# BSB-to-Wifi.net
KiCad netlist of a schematic drawn in EAGLE
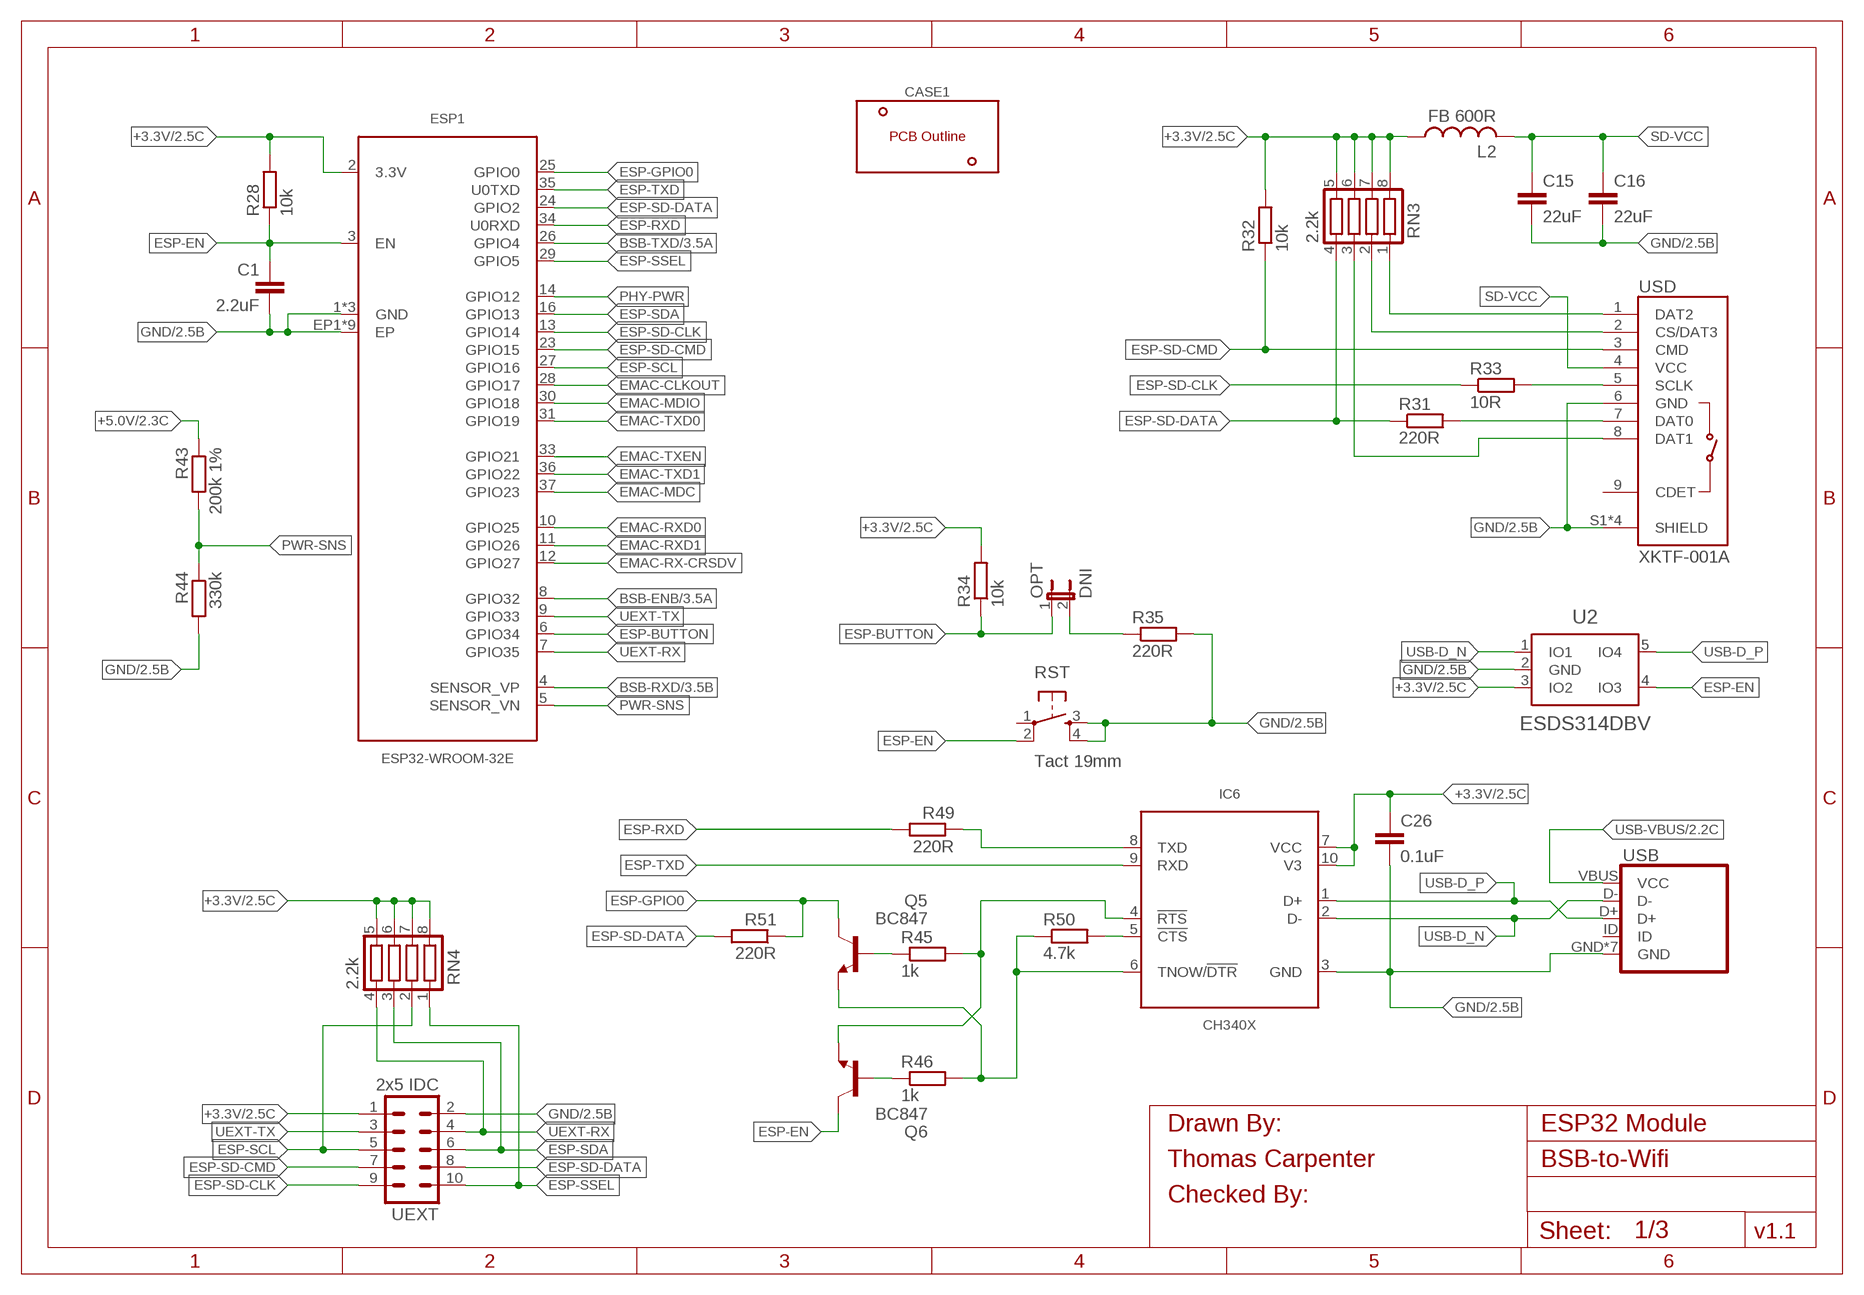
[diagram p0: schematic, sheet 1]
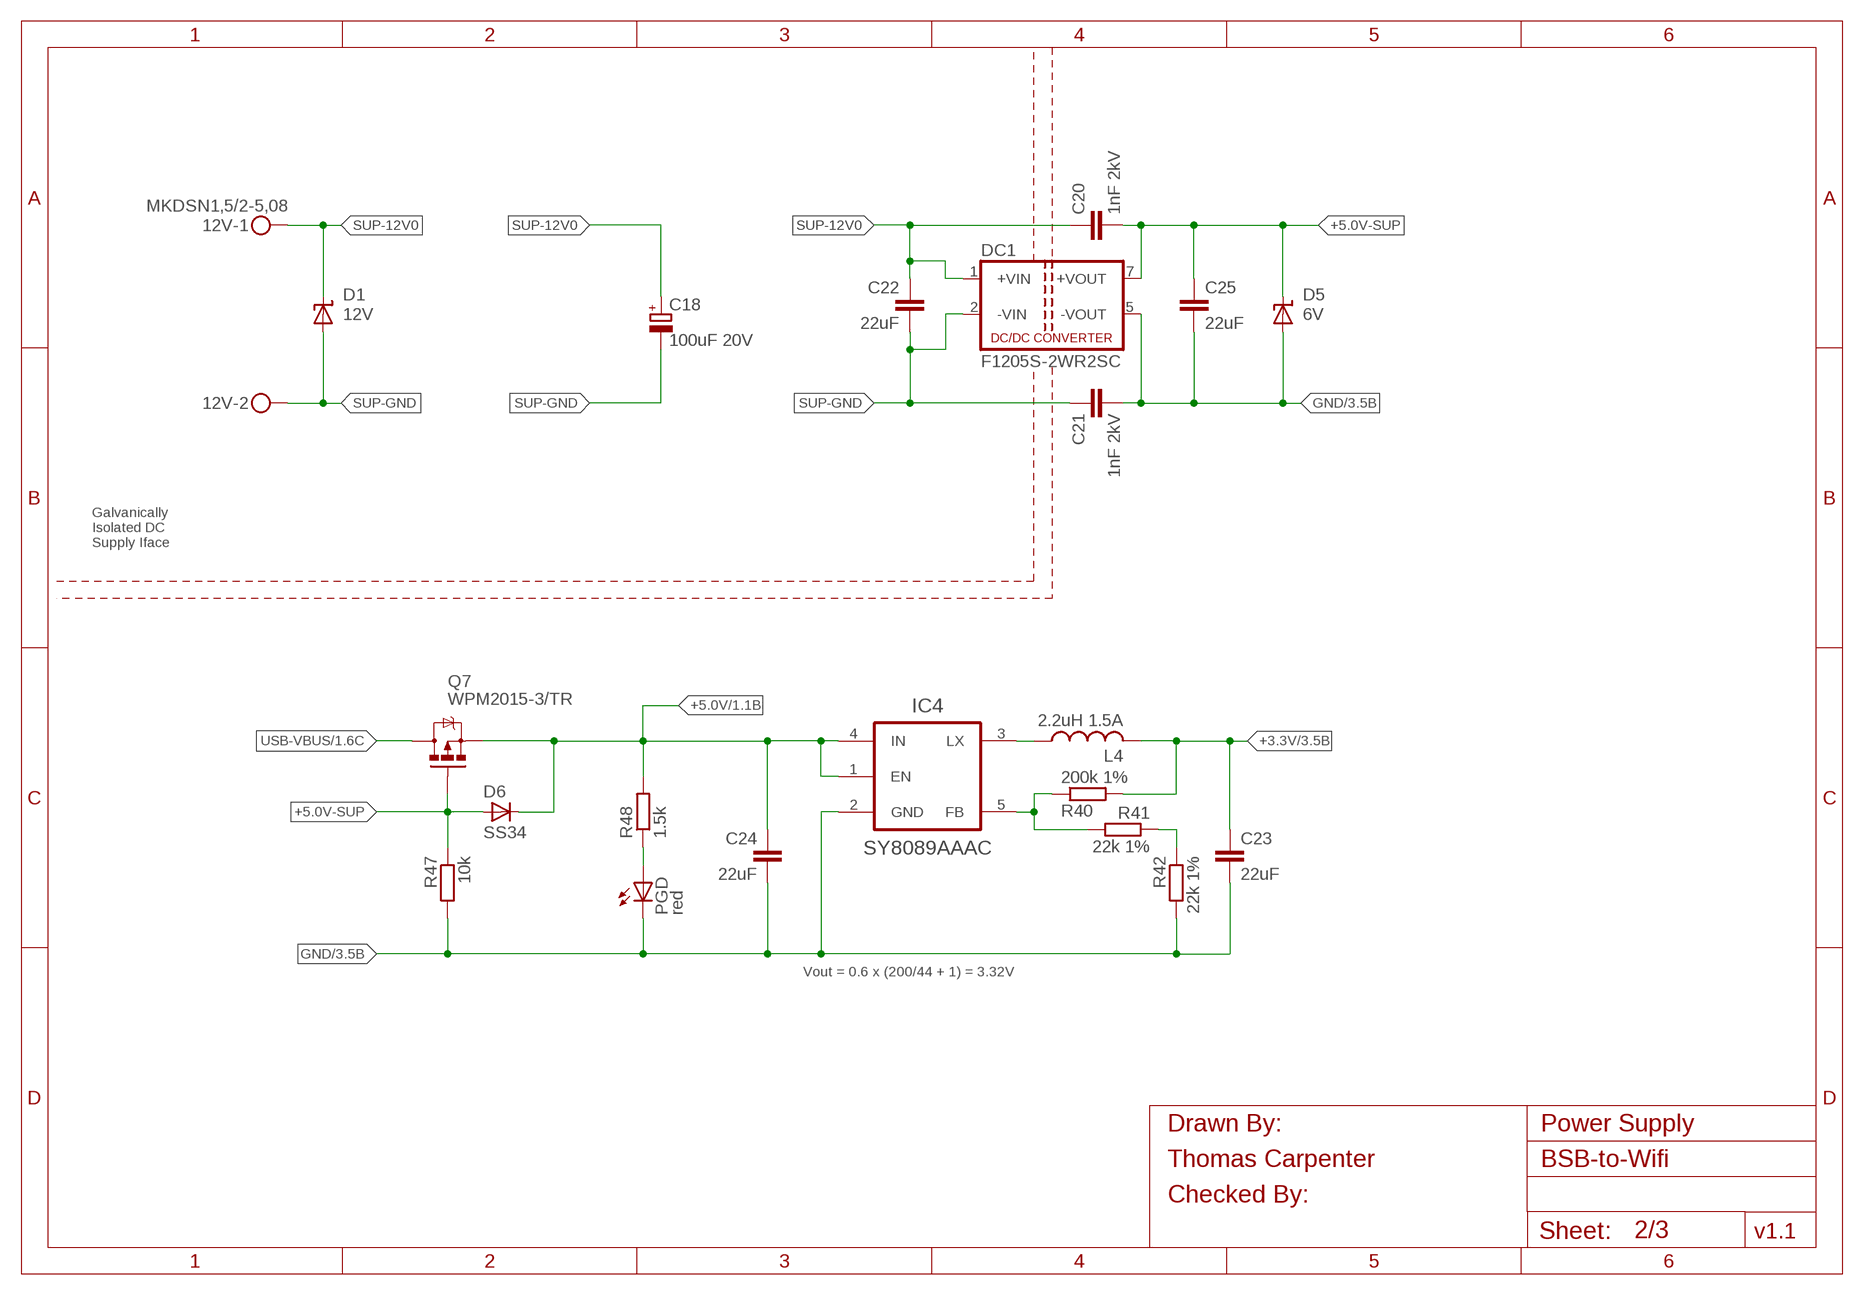
[diagram p1: schematic, sheet 2]
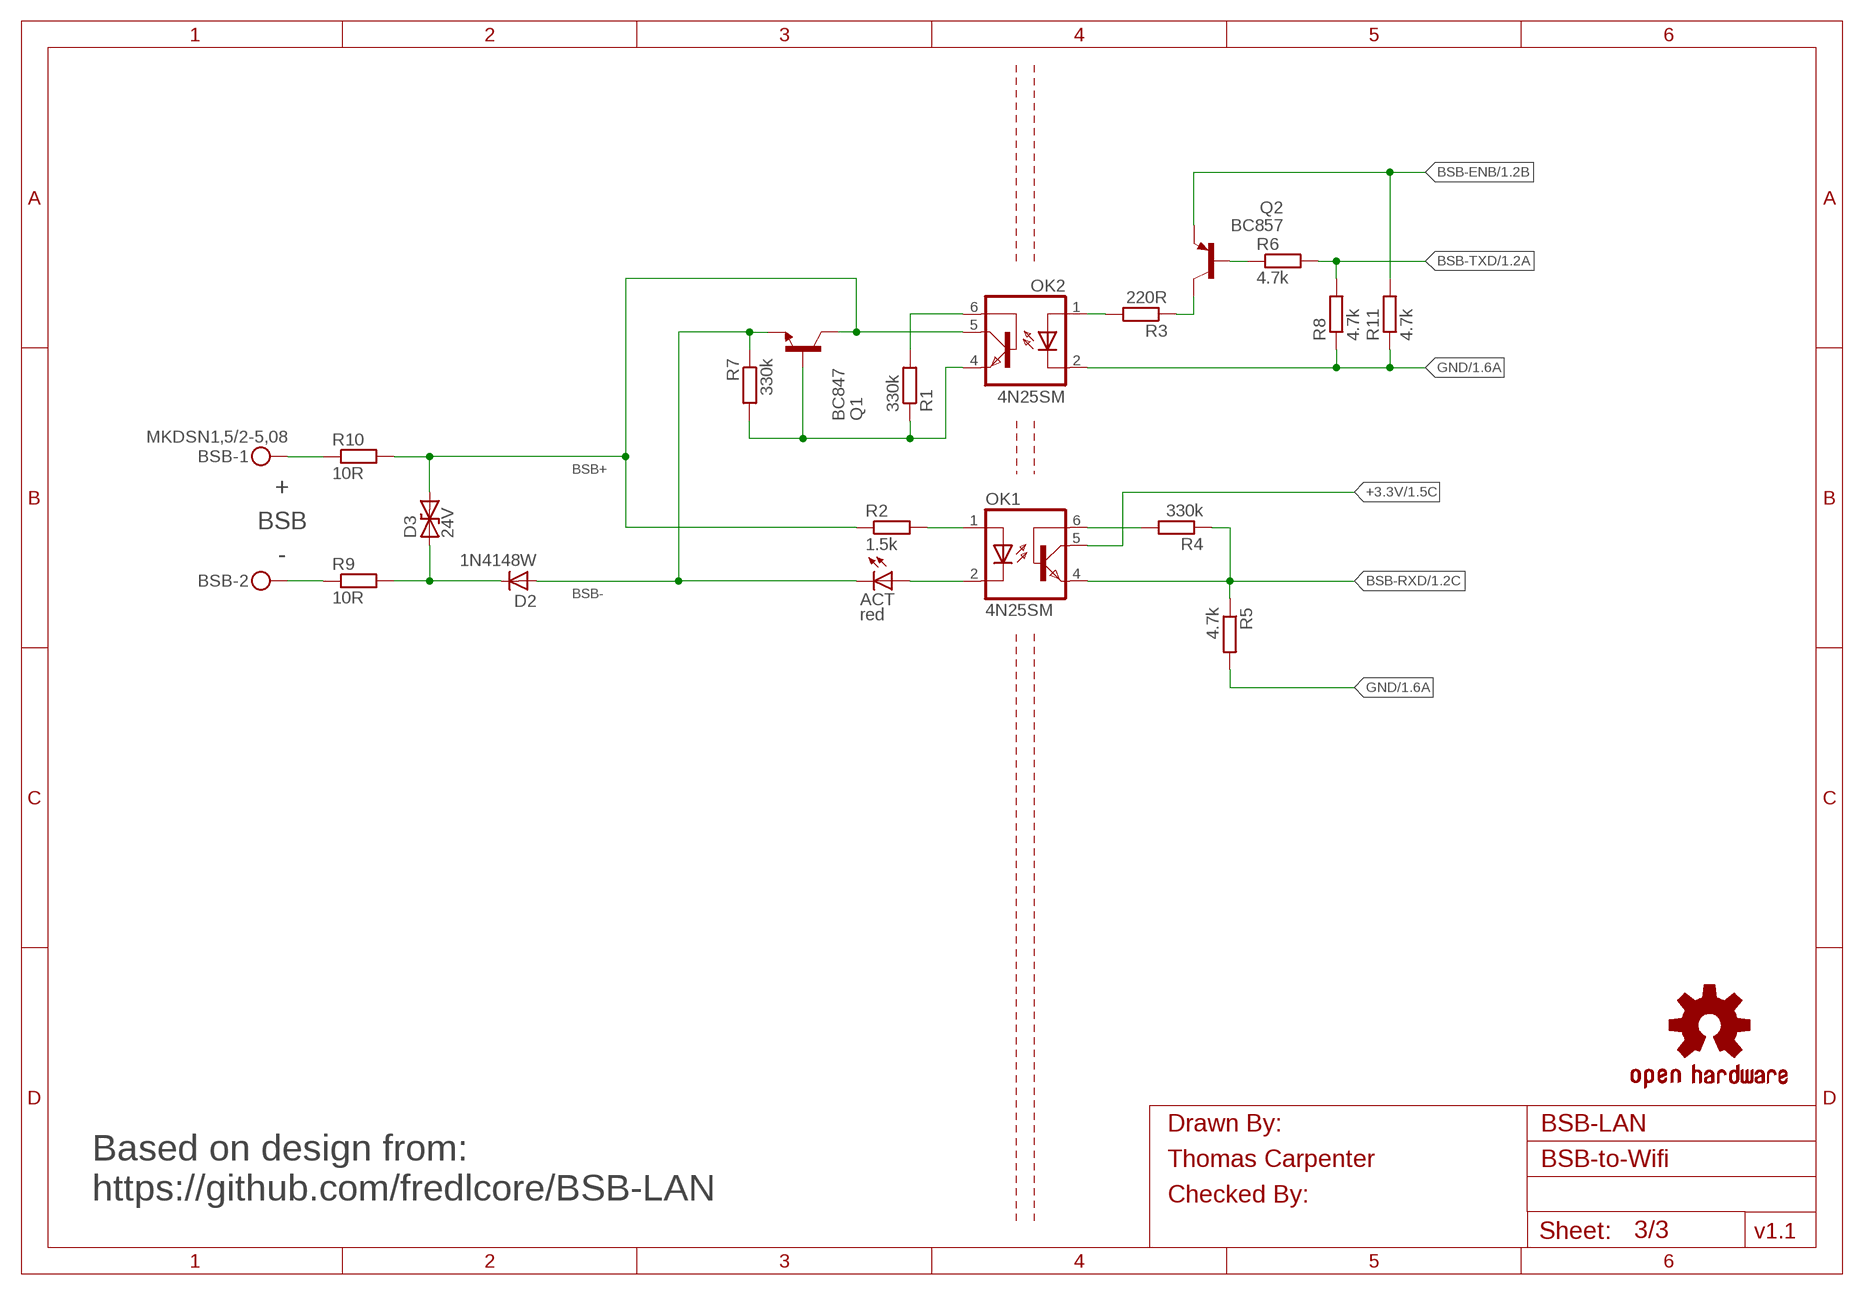
[diagram p2: schematic, sheet 3]

(export (version "E")
  (design (tool "Eeschema 10.0.6"))
  (components
    (comp (ref "C1")
      (value "2.2uF")
      (footprint "eagle-import:C0603")
      (fields (field (name "LCSC_PART") "C23630"))
      (libsource (lib "eagle-import") (part "C-EUC0603"))
    )
    (comp (ref "C15")
      (value "22uF")
      (footprint "eagle-import:C0805L")
      (fields (field (name "LCSC_PART") "C45783"))
      (libsource (lib "eagle-import") (part "C-EUC0805L"))
    )
    (comp (ref "C16")
      (value "22uF")
      (footprint "eagle-import:C0805L")
      (fields (field (name "LCSC_PART") "C45783"))
      (libsource (lib "eagle-import") (part "C-EUC0805L"))
    )
    (comp (ref "C26")
      (value "0.1uF")
      (footprint "eagle-import:C0402")
      (fields (field (name "LCSC_PART") "C1525"))
      (libsource (lib "eagle-import") (part "C-EUC0402"))
    )
    (comp (ref "CASE1")
      (value "DNI")
      (footprint "eagle-import:CNMB_2-")
      (libsource (lib "eagle-import") (part "CNMB/2"))
    )
    (comp (ref "ESP1")
      (value "ESP32-WROOM-32E")
      (footprint "eagle-import:ESP32-WROOM-32E")
      (fields (field (name "LCSC_PART") "C701341"))
      (libsource (lib "eagle-import") (part "ESP32-WROOM-32E"))
    )
    (comp (ref "IC6")
      (value "CH340X")
      (footprint "eagle-import:MSOP10")
      (fields (field (name "LCSC_PART") "C3035748"))
      (libsource (lib "eagle-import") (part "CH340X"))
    )
    (comp (ref "L2")
      (value "FB 600R")
      (footprint "eagle-import:L2010")
      (fields (field (name "LCSC_PART") "C1017"))
      (libsource (lib "eagle-import") (part "L-USL0805"))
    )
    (comp (ref "OPT")
      (value "DNI")
      (footprint "eagle-import:1X02")
      (libsource (lib "eagle-import") (part "JUMPER-2-PTH"))
    )
    (comp (ref "Q5")
      (value "BC847")
      (footprint "eagle-import:SOT23")
      (fields (field (name "LCSC_PART") "C130417") (field (name "LCSC_PART_1") "C130417"))
      (libsource (lib "eagle-import") (part "BC847"))
    )
    (comp (ref "Q6")
      (value "BC847")
      (footprint "eagle-import:SOT23")
      (fields (field (name "LCSC_PART") "C130417"))
      (libsource (lib "eagle-import") (part "BC847"))
    )
    (comp (ref "R28")
      (value "10k")
      (footprint "eagle-import:R0402")
      (fields (field (name "LCSC_PART") "C25744"))
      (libsource (lib "eagle-import") (part "R-EU_R0402"))
    )
    (comp (ref "R31")
      (value "220R")
      (footprint "eagle-import:R0402")
      (fields (field (name "LCSC_PART") "C25091"))
      (libsource (lib "eagle-import") (part "R-EU_R0402"))
    )
    (comp (ref "R32")
      (value "10k")
      (footprint "eagle-import:R0402")
      (fields (field (name "LCSC_PART") "C25744"))
      (libsource (lib "eagle-import") (part "R-EU_R0402"))
    )
    (comp (ref "R33")
      (value "10R")
      (footprint "eagle-import:R0603L")
      (fields (field (name "LCSC_PART") "C22859"))
      (libsource (lib "eagle-import") (part "R-EU_R0603L"))
    )
    (comp (ref "R34")
      (value "10k")
      (footprint "eagle-import:R0402")
      (fields (field (name "LCSC_PART") "C25744"))
      (libsource (lib "eagle-import") (part "R-EU_R0402"))
    )
    (comp (ref "R35")
      (value "220R")
      (footprint "eagle-import:R0402")
      (fields (field (name "LCSC_PART") "C25091"))
      (libsource (lib "eagle-import") (part "R-EU_R0402"))
    )
    (comp (ref "R43")
      (value "200k 1%")
      (footprint "eagle-import:R0402")
      (fields (field (name "LCSC_PART") "C25764"))
      (libsource (lib "eagle-import") (part "R-EU_R0402"))
    )
    (comp (ref "R44")
      (value "330k")
      (footprint "eagle-import:R0603L")
      (fields (field (name "LCSC_PART") "C23137"))
      (libsource (lib "eagle-import") (part "R-EU_R0603L"))
    )
    (comp (ref "R45")
      (value "1k")
      (footprint "eagle-import:R0402")
      (fields (field (name "LCSC_PART") "C11702"))
      (libsource (lib "eagle-import") (part "R-EU_R0402"))
    )
    (comp (ref "R46")
      (value "1k")
      (footprint "eagle-import:R0402")
      (fields (field (name "LCSC_PART") "C11702"))
      (libsource (lib "eagle-import") (part "R-EU_R0402"))
    )
    (comp (ref "R49")
      (value "220R")
      (footprint "eagle-import:R0402")
      (fields (field (name "LCSC_PART") "C25091"))
      (libsource (lib "eagle-import") (part "R-EU_R0402"))
    )
    (comp (ref "R50")
      (value "4.7k")
      (footprint "eagle-import:R0402")
      (fields (field (name "LCSC_PART") "C25900"))
      (libsource (lib "eagle-import") (part "R-EU_R0402"))
    )
    (comp (ref "R51")
      (value "220R")
      (footprint "eagle-import:R0402")
      (fields (field (name "LCSC_PART") "C25091"))
      (libsource (lib "eagle-import") (part "R-EU_R0402"))
    )
    (comp (ref "RN3")
      (value "2.2k")
      (footprint "eagle-import:CTS742C083")
      (fields (field (name "LCSC_PART") "C414564"))
      (libsource (lib "eagle-import") (part "R-NET-04-R1206"))
    )
    (comp (ref "RN4")
      (value "2.2k")
      (footprint "eagle-import:CTS742C083")
      (fields (field (name "LCSC_PART") "C414564"))
      (libsource (lib "eagle-import") (part "R-NET-04-R1206"))
    )
    (comp (ref "RST")
      (value "Tact 19mm")
      (footprint "eagle-import:TACTILE_SWITCH")
      (fields (field (name "LCSC_PART") "C13828") (field (name "LCSC_PART_1") "C2837529"))
      (libsource (lib "eagle-import") (part "SWITCH-MOMENTARY"))
    )
    (comp (ref "U2")
      (value "ESDS314DBV")
      (footprint "eagle-import:DBV0005A-SOT23")
      (fields (field (name "LCSC_PART") "C1847859"))
      (libsource (lib "eagle-import") (part "ESDS314DBV"))
    )
    (comp (ref "UEXT")
      (value "2x5 IDC")
      (footprint "eagle-import:ML10")
      (fields (field (name "LCSC_PART") "C5665"))
      (libsource (lib "eagle-import") (part "ML10"))
    )
    (comp (ref "USB")
      (value "ZX62-B-5PA(33)")
      (footprint "eagle-import:USB-MICROB")
      (fields (field (name "LCSC_PART") "C132561"))
      (libsource (lib "eagle-import") (part "USB_MICROB_PLUG"))
    )
    (comp (ref "USD")
      (value "XKTF-001A")
      (footprint "eagle-import:MICRO-SD")
      (fields (field (name "LCSC_PART") "C381079"))
      (libsource (lib "eagle-import") (part "MICROSD"))
    )
    (comp (ref "12V")
      (value "MKDSN1,5/2-5,08")
      (footprint "eagle-import:MKDSN1_5-2-5_08")
      (fields (field (name "LCSC_PART") "C5183989"))
      (libsource (lib "eagle-import") (part "MKDSN1,5/2-5,08"))
    )
    (comp (ref "C18")
      (value "100uF 20V")
      (footprint "eagle-import:SMC_D")
      (fields (field (name "LCSC_PART") "C7224"))
      (libsource (lib "eagle-import") (part "CPOL-EUSMCD"))
    )
    (comp (ref "C20")
      (value "1nF 2kV")
      (footprint "eagle-import:C1206L")
      (fields (field (name "LCSC_PART") "C9196"))
      (libsource (lib "eagle-import") (part "C-EUC1206L"))
    )
    (comp (ref "C21")
      (value "1nF 2kV")
      (footprint "eagle-import:C1206L")
      (fields (field (name "LCSC_PART") "C9196"))
      (libsource (lib "eagle-import") (part "C-EUC1206L"))
    )
    (comp (ref "C22")
      (value "22uF")
      (footprint "eagle-import:C0805")
      (fields (field (name "LCSC_PART") "C45783"))
      (libsource (lib "eagle-import") (part "C-EUC0805"))
    )
    (comp (ref "C23")
      (value "22uF")
      (footprint "eagle-import:C0805")
      (fields (field (name "LCSC_PART") "C45783"))
      (libsource (lib "eagle-import") (part "C-EUC0805"))
    )
    (comp (ref "C24")
      (value "22uF")
      (footprint "eagle-import:C0805")
      (fields (field (name "LCSC_PART") "C45783"))
      (libsource (lib "eagle-import") (part "C-EUC0805"))
    )
    (comp (ref "C25")
      (value "22uF")
      (footprint "eagle-import:C0805")
      (fields (field (name "LCSC_PART") "C45783"))
      (libsource (lib "eagle-import") (part "C-EUC0805"))
    )
    (comp (ref "D1")
      (value "12V")
      (footprint "eagle-import:SMA")
      (fields (field (name "LCSC_PART") "C148213"))
      (libsource (lib "eagle-import") (part "TVS-UNISMA"))
    )
    (comp (ref "D5")
      (value "6V")
      (footprint "eagle-import:SMA")
      (fields (field (name "LCSC_PART") "C223993"))
      (libsource (lib "eagle-import") (part "TVS-UNISMA"))
    )
    (comp (ref "D6")
      (value "SS34")
      (footprint "eagle-import:SMA")
      (fields (field (name "LCSC_PART") "C8678"))
      (libsource (lib "eagle-import") (part "DIODE-SMA"))
    )
    (comp (ref "DC1")
      (value "F1205S-2WR2SC")
      (footprint "eagle-import:SIP7-N")
      (fields (field (name "LCSC_PART") "C5369565"))
      (libsource (lib "eagle-import") (part "FS-2WR2SC1205"))
    )
    (comp (ref "IC4")
      (value "SY8089AAAC")
      (footprint "eagle-import:DBV0005A-SOT23")
      (fields (field (name "LCSC_PART") "C78988"))
      (libsource (lib "eagle-import") (part "SY8089?CAAA"))
    )
    (comp (ref "L4")
      (value "2.2uH 1.5A")
      (footprint "eagle-import:L4040P")
      (fields (field (name "LCSC_PART") "C135262"))
      (libsource (lib "eagle-import") (part "L-USL4040P"))
    )
    (comp (ref "PGD")
      (value "red")
      (footprint "eagle-import:CHIP-LED0603")
      (fields (field (name "LCSC_PART") "C2286"))
      (libsource (lib "eagle-import") (part "LEDCHIPLED_0603"))
    )
    (comp (ref "Q7")
      (value "WPM2015-3/TR")
      (footprint "eagle-import:SOT23")
      (fields (field (name "LCSC_PART") "C7472861"))
      (libsource (lib "eagle-import") (part "WPM2015-3/TR"))
    )
    (comp (ref "R40")
      (value "200k 1%")
      (footprint "eagle-import:R0402")
      (fields (field (name "LCSC_PART") "C25764"))
      (libsource (lib "eagle-import") (part "R-EU_R0402"))
    )
    (comp (ref "R41")
      (value "22k 1%")
      (footprint "eagle-import:R0402")
      (fields (field (name "LCSC_PART") "C25768"))
      (libsource (lib "eagle-import") (part "R-EU_R0402"))
    )
    (comp (ref "R42")
      (value "22k 1%")
      (footprint "eagle-import:R0402")
      (fields (field (name "LCSC_PART") "C25768"))
      (libsource (lib "eagle-import") (part "R-EU_R0402"))
    )
    (comp (ref "R47")
      (value "10k")
      (footprint "eagle-import:R0402")
      (fields (field (name "LCSC_PART") "C25744"))
      (libsource (lib "eagle-import") (part "R-EU_R0402"))
    )
    (comp (ref "R48")
      (value "1.5k")
      (footprint "eagle-import:R0603")
      (fields (field (name "LCSC_PART") "C22843"))
      (libsource (lib "eagle-import") (part "R-EU_R0603"))
    )
    (comp (ref "ACT")
      (value "red")
      (footprint "eagle-import:CHIP-LED0603")
      (fields (field (name "LCSC_PART") "C2286"))
      (libsource (lib "eagle-import") (part "LEDCHIPLED_0603"))
    )
    (comp (ref "BSB")
      (value "MKDSN1,5/2-5,08")
      (footprint "eagle-import:MKDSN1_5-2-5_08")
      (fields (field (name "LCSC_PART") "C5183989"))
      (libsource (lib "eagle-import") (part "MKDSN1,5/2-5,08"))
    )
    (comp (ref "D2")
      (value "1N4148W")
      (footprint "eagle-import:SOD123")
      (fields (field (name "LCSC_PART") "C81598"))
      (libsource (lib "eagle-import") (part "DIODE-SOD123"))
    )
    (comp (ref "D3")
      (value "24V")
      (footprint "eagle-import:SMBG")
      (fields (field (name "LCSC_PART") "C83268"))
      (libsource (lib "eagle-import") (part "TVS-BIDIRSMB"))
    )
    (comp (ref "OK1")
      (value "4N25SM")
      (footprint "eagle-import:DIL6-SMD")
      (fields (field (name "LCSC_PART") "C258246") (field (name "LCSC_PART_1") "C258246"))
      (libsource (lib "eagle-import") (part "4N?MS25"))
    )
    (comp (ref "OK2")
      (value "4N25SM")
      (footprint "eagle-import:DIL6-SMD")
      (fields (field (name "LCSC_PART") "C258246") (field (name "LCSC_PART_1") "C258246"))
      (libsource (lib "eagle-import") (part "4N?MS25"))
    )
    (comp (ref "Q1")
      (value "BC847")
      (footprint "eagle-import:SOT23")
      (fields (field (name "LCSC_PART") "C130417") (field (name "LCSC_PART_1") "C130417"))
      (libsource (lib "eagle-import") (part "BC847"))
    )
    (comp (ref "Q2")
      (value "BC857")
      (footprint "eagle-import:SOT23-BEC")
      (fields (field (name "LCSC_PART") "C426782") (field (name "LCSC_PART_1") "C426782"))
      (libsource (lib "eagle-import") (part "BC857"))
    )
    (comp (ref "R1")
      (value "330k")
      (footprint "eagle-import:R0603")
      (fields (field (name "LCSC_PART") "C23137"))
      (libsource (lib "eagle-import") (part "R-EU_R0603"))
    )
    (comp (ref "R2")
      (value "1.5k")
      (footprint "eagle-import:R0603")
      (fields (field (name "LCSC_PART") "C22843"))
      (libsource (lib "eagle-import") (part "R-EU_R0603"))
    )
    (comp (ref "R3")
      (value "220R")
      (footprint "eagle-import:R0402")
      (fields (field (name "LCSC_PART") "C25091"))
      (libsource (lib "eagle-import") (part "R-EU_R0402"))
    )
    (comp (ref "R4")
      (value "330k")
      (footprint "eagle-import:R0603")
      (fields (field (name "LCSC_PART") "C23137"))
      (libsource (lib "eagle-import") (part "R-EU_R0603"))
    )
    (comp (ref "R5")
      (value "4.7k")
      (footprint "eagle-import:R0402")
      (fields (field (name "LCSC_PART") "C25900"))
      (libsource (lib "eagle-import") (part "R-EU_R0402"))
    )
    (comp (ref "R6")
      (value "4.7k")
      (footprint "eagle-import:R0402")
      (fields (field (name "LCSC_PART") "C25900"))
      (libsource (lib "eagle-import") (part "R-EU_R0402"))
    )
    (comp (ref "R7")
      (value "330k")
      (footprint "eagle-import:R0603")
      (fields (field (name "LCSC_PART") "C23137"))
      (libsource (lib "eagle-import") (part "R-EU_R0603"))
    )
    (comp (ref "R8")
      (value "4.7k")
      (footprint "eagle-import:R0402")
      (fields (field (name "LCSC_PART") "C25900"))
      (libsource (lib "eagle-import") (part "R-EU_R0402"))
    )
    (comp (ref "R9")
      (value "10R")
      (footprint "eagle-import:R0603")
      (fields (field (name "LCSC_PART") "C22859"))
      (libsource (lib "eagle-import") (part "R-EU_R0603"))
    )
    (comp (ref "R10")
      (value "10R")
      (footprint "eagle-import:R0603")
      (fields (field (name "LCSC_PART") "C22859"))
      (libsource (lib "eagle-import") (part "R-EU_R0603"))
    )
    (comp (ref "R11")
      (value "4.7k")
      (footprint "eagle-import:R0402")
      (fields (field (name "LCSC_PART") "C25900"))
      (libsource (lib "eagle-import") (part "R-EU_R0402"))
    )
    (comp (ref "U$3")
      (value "DNI")
      (footprint "eagle-import:OSHW-LOGO-M")
      (libsource (lib "eagle-import") (part "OSHW-LOGOM"))
    )
  )
  (nets
    (net (code "1") (name "+3.3V") (class "Default")
      (node (ref "C23") (pin "1") (pinfunction "1_1") (pintype "passive"))
      (node (ref "C26") (pin "1") (pinfunction "1_1") (pintype "passive"))
      (node (ref "ESP1") (pin "2") (pinfunction "3.3V_2") (pintype "power_in"))
      (node (ref "IC6") (pin "10") (pinfunction "V3_10") (pintype "power_in"))
      (node (ref "IC6") (pin "7") (pinfunction "VCC_7") (pintype "power_in"))
      (node (ref "L2") (pin "1") (pinfunction "1_1") (pintype "passive"))
      (node (ref "L4") (pin "2") (pinfunction "2_2") (pintype "passive"))
      (node (ref "OK1") (pin "5") (pinfunction "COL_5") (pintype "passive"))
      (node (ref "R28") (pin "2") (pinfunction "2_2") (pintype "passive"))
      (node (ref "R32") (pin "2") (pinfunction "2_2") (pintype "passive"))
      (node (ref "R34") (pin "2") (pinfunction "2_2") (pintype "passive"))
      (node (ref "R40") (pin "2") (pinfunction "2_2") (pintype "passive"))
      (node (ref "RN3") (pin "5") (pinfunction "5_5") (pintype "passive"))
      (node (ref "RN3") (pin "6") (pinfunction "6_6") (pintype "passive"))
      (node (ref "RN3") (pin "7") (pinfunction "7_7") (pintype "passive"))
      (node (ref "RN3") (pin "8") (pinfunction "8_8") (pintype "passive"))
      (node (ref "RN4") (pin "5") (pinfunction "5_5") (pintype "passive"))
      (node (ref "RN4") (pin "6") (pinfunction "6_6") (pintype "passive"))
      (node (ref "RN4") (pin "7") (pinfunction "7_7") (pintype "passive"))
      (node (ref "RN4") (pin "8") (pinfunction "8_8") (pintype "passive"))
      (node (ref "U2") (pin "3") (pinfunction "IO2_3") (pintype "passive"))
      (node (ref "UEXT") (pin "1") (pinfunction "1_1") (pintype "passive"))
    )
    (net (code "2") (name "+5.0V") (class "Default")
      (node (ref "C24") (pin "1") (pinfunction "1_1") (pintype "passive"))
      (node (ref "D6") (pin "C") (pinfunction "C_C") (pintype "passive"))
      (node (ref "IC4") (pin "1") (pinfunction "EN_1") (pintype "input"))
      (node (ref "IC4") (pin "4") (pinfunction "IN_4") (pintype "power_in"))
      (node (ref "Q7") (pin "2") (pinfunction "S_2") (pintype "passive"))
      (node (ref "R43") (pin "1") (pinfunction "1_1") (pintype "passive"))
      (node (ref "R48") (pin "2") (pinfunction "2_2") (pintype "passive"))
    )
    (net (code "3") (name "+5.0V-SUP") (class "Default")
      (node (ref "C20") (pin "2") (pinfunction "2_2") (pintype "passive"))
      (node (ref "C25") (pin "1") (pinfunction "1_1") (pintype "passive"))
      (node (ref "D5") (pin "C") (pinfunction "C_C") (pintype "passive"))
      (node (ref "D6") (pin "A") (pinfunction "A_A") (pintype "passive"))
      (node (ref "DC1") (pin "7") (pinfunction "+VOUT_7") (pintype "passive"))
      (node (ref "Q7") (pin "1") (pinfunction "G_1") (pintype "passive"))
      (node (ref "R47") (pin "1") (pinfunction "1_1") (pintype "passive"))
    )
    (net (code "4") (name "BSB+") (class "Default")
      (node (ref "D3") (pin "2") (pinfunction "2_2") (pintype "passive"))
      (node (ref "OK2") (pin "5") (pinfunction "COL_5") (pintype "passive"))
      (node (ref "Q1") (pin "3") (pinfunction "C_3") (pintype "passive"))
      (node (ref "R10") (pin "2") (pinfunction "2_2") (pintype "passive"))
      (node (ref "R2") (pin "1") (pinfunction "1_1") (pintype "passive"))
    )
    (net (code "5") (name "BSB-") (class "Default")
      (node (ref "ACT") (pin "C") (pinfunction "C_C") (pintype "passive"))
      (node (ref "D2") (pin "A") (pinfunction "A_A") (pintype "passive"))
      (node (ref "Q1") (pin "2") (pinfunction "E_2") (pintype "passive"))
      (node (ref "R7") (pin "1") (pinfunction "1_1") (pintype "passive"))
    )
    (net (code "6") (name "BSB-ENB") (class "Default")
      (node (ref "ESP1") (pin "8") (pinfunction "GPIO32_8") (pintype "bidirectional"))
      (node (ref "Q2") (pin "E") (pinfunction "E_E") (pintype "passive"))
      (node (ref "R11") (pin "2") (pinfunction "2_2") (pintype "passive"))
    )
    (net (code "7") (name "BSB-RXD") (class "Default")
      (node (ref "ESP1") (pin "4") (pinfunction "SENSOR_VP_4") (pintype "bidirectional"))
      (node (ref "OK1") (pin "4") (pinfunction "EMI_4") (pintype "passive"))
      (node (ref "R4") (pin "1") (pinfunction "1_1") (pintype "passive"))
      (node (ref "R5") (pin "1") (pinfunction "1_1") (pintype "passive"))
    )
    (net (code "8") (name "BSB-TXD") (class "Default")
      (node (ref "ESP1") (pin "26") (pinfunction "GPIO4_26") (pintype "bidirectional"))
      (node (ref "R6") (pin "2") (pinfunction "2_2") (pintype "passive"))
      (node (ref "R8") (pin "2") (pinfunction "2_2") (pintype "passive"))
    )
    (net (code "9") (name "EMAC-CLKOUT") (class "Default")
      (node (ref "ESP1") (pin "28") (pinfunction "GPIO17_28") (pintype "bidirectional"))
    )
    (net (code "10") (name "EMAC-MDC") (class "Default")
      (node (ref "ESP1") (pin "37") (pinfunction "GPIO23_37") (pintype "bidirectional"))
    )
    (net (code "11") (name "EMAC-MDIO") (class "Default")
      (node (ref "ESP1") (pin "30") (pinfunction "GPIO18_30") (pintype "bidirectional"))
    )
    (net (code "12") (name "EMAC-RX-CRSDV") (class "Default")
      (node (ref "ESP1") (pin "12") (pinfunction "GPIO27_12") (pintype "bidirectional"))
    )
    (net (code "13") (name "EMAC-RXD0") (class "Default")
      (node (ref "ESP1") (pin "10") (pinfunction "GPIO25_10") (pintype "bidirectional"))
    )
    (net (code "14") (name "EMAC-RXD1") (class "Default")
      (node (ref "ESP1") (pin "11") (pinfunction "GPIO26_11") (pintype "bidirectional"))
    )
    (net (code "15") (name "EMAC-TXD0") (class "Default")
      (node (ref "ESP1") (pin "31") (pinfunction "GPIO19_31") (pintype "bidirectional"))
    )
    (net (code "16") (name "EMAC-TXD1") (class "Default")
      (node (ref "ESP1") (pin "36") (pinfunction "GPIO22_36") (pintype "bidirectional"))
    )
    (net (code "17") (name "EMAC-TXEN") (class "Default")
      (node (ref "ESP1") (pin "33") (pinfunction "GPIO21_33") (pintype "bidirectional"))
    )
    (net (code "18") (name "ESP-BUTTON") (class "Default")
      (node (ref "ESP1") (pin "6") (pinfunction "GPIO34_6") (pintype "bidirectional"))
      (node (ref "OPT") (pin "1") (pinfunction "1_1") (pintype "passive"))
      (node (ref "R34") (pin "1") (pinfunction "1_1") (pintype "passive"))
    )
    (net (code "19") (name "ESP-EN") (class "Default")
      (node (ref "C1") (pin "1") (pinfunction "1_1") (pintype "passive"))
      (node (ref "ESP1") (pin "3") (pinfunction "EN_3") (pintype "input"))
      (node (ref "Q6") (pin "3") (pinfunction "C_3") (pintype "passive"))
      (node (ref "R28") (pin "1") (pinfunction "1_1") (pintype "passive"))
      (node (ref "RST") (pin "2") (pinfunction "2_2") (pintype "passive"))
      (node (ref "U2") (pin "4") (pinfunction "IO3_4") (pintype "passive"))
    )
    (net (code "20") (name "ESP-GPIO0") (class "Default")
      (node (ref "ESP1") (pin "25") (pinfunction "GPIO0_25") (pintype "bidirectional"))
      (node (ref "Q5") (pin "3") (pinfunction "C_3") (pintype "passive"))
      (node (ref "R51") (pin "1") (pinfunction "1_1") (pintype "passive"))
    )
    (net (code "21") (name "ESP-RXD") (class "Default")
      (node (ref "ESP1") (pin "34") (pinfunction "U0RXD_34") (pintype "bidirectional"))
      (node (ref "R49") (pin "2") (pinfunction "2_2") (pintype "passive"))
    )
    (net (code "22") (name "ESP-SCL") (class "Default")
      (node (ref "ESP1") (pin "27") (pinfunction "GPIO16_27") (pintype "bidirectional"))
      (node (ref "RN4") (pin "2") (pinfunction "2_2") (pintype "passive"))
      (node (ref "UEXT") (pin "5") (pinfunction "5_5") (pintype "passive"))
    )
    (net (code "23") (name "ESP-SD-CLK") (class "Default")
      (node (ref "ESP1") (pin "13") (pinfunction "GPIO14_13") (pintype "bidirectional"))
      (node (ref "R33") (pin "1") (pinfunction "1_1") (pintype "passive"))
      (node (ref "UEXT") (pin "9") (pinfunction "9_9") (pintype "passive"))
    )
    (net (code "24") (name "ESP-SD-CMD") (class "Default")
      (node (ref "ESP1") (pin "23") (pinfunction "GPIO15_23") (pintype "bidirectional"))
      (node (ref "R32") (pin "1") (pinfunction "1_1") (pintype "passive"))
      (node (ref "UEXT") (pin "7") (pinfunction "7_7") (pintype "passive"))
      (node (ref "USD") (pin "3") (pinfunction "CMD_3") (pintype "bidirectional"))
    )
    (net (code "25") (name "ESP-SD-DATA") (class "Default")
      (node (ref "ESP1") (pin "24") (pinfunction "GPIO2_24") (pintype "bidirectional"))
      (node (ref "R31") (pin "1") (pinfunction "1_1") (pintype "passive"))
      (node (ref "R51") (pin "2") (pinfunction "2_2") (pintype "passive"))
      (node (ref "RN3") (pin "4") (pinfunction "4_4") (pintype "passive"))
      (node (ref "UEXT") (pin "8") (pinfunction "8_8") (pintype "passive"))
    )
    (net (code "26") (name "ESP-SDA") (class "Default")
      (node (ref "ESP1") (pin "16") (pinfunction "GPIO13_16") (pintype "bidirectional"))
      (node (ref "RN4") (pin "3") (pinfunction "3_3") (pintype "passive"))
      (node (ref "UEXT") (pin "6") (pinfunction "6_6") (pintype "passive"))
    )
    (net (code "27") (name "ESP-SSEL") (class "Default")
      (node (ref "ESP1") (pin "29") (pinfunction "GPIO5_29") (pintype "bidirectional"))
      (node (ref "RN4") (pin "1") (pinfunction "1_1") (pintype "passive"))
      (node (ref "UEXT") (pin "10") (pinfunction "10_10") (pintype "passive"))
    )
    (net (code "28") (name "ESP-TXD") (class "Default")
      (node (ref "ESP1") (pin "35") (pinfunction "U0TXD_35") (pintype "bidirectional"))
      (node (ref "IC6") (pin "9") (pinfunction "RXD_9") (pintype "input"))
    )
    (net (code "29") (name "GND") (class "Default")
      (node (ref "C1") (pin "2") (pinfunction "2_2") (pintype "passive"))
      (node (ref "C15") (pin "2") (pinfunction "2_2") (pintype "passive"))
      (node (ref "C16") (pin "2") (pinfunction "2_2") (pintype "passive"))
      (node (ref "C21") (pin "2") (pinfunction "2_2") (pintype "passive"))
      (node (ref "C23") (pin "2") (pinfunction "2_2") (pintype "passive"))
      (node (ref "C24") (pin "2") (pinfunction "2_2") (pintype "passive"))
      (node (ref "C25") (pin "2") (pinfunction "2_2") (pintype "passive"))
      (node (ref "C26") (pin "2") (pinfunction "2_2") (pintype "passive"))
      (node (ref "D5") (pin "A") (pinfunction "A_A") (pintype "passive"))
      (node (ref "DC1") (pin "5") (pinfunction "-VOUT_5") (pintype "passive"))
      (node (ref "ESP1") (pin "1") (pinfunction "GND_1") (pintype "power_in"))
      (node (ref "ESP1") (pin "15") (pinfunction "GND_15") (pintype "power_in"))
      (node (ref "ESP1") (pin "38") (pinfunction "GND_38") (pintype "power_in"))
      (node (ref "ESP1") (pin "EP1") (pinfunction "EP_EP1") (pintype "passive"))
      (node (ref "ESP1") (pin "EP2") (pinfunction "EP_EP2") (pintype "passive"))
      (node (ref "ESP1") (pin "EP3") (pinfunction "EP_EP3") (pintype "passive"))
      (node (ref "ESP1") (pin "EP4") (pinfunction "EP_EP4") (pintype "passive"))
      (node (ref "ESP1") (pin "EP5") (pinfunction "EP_EP5") (pintype "passive"))
      (node (ref "ESP1") (pin "EP6") (pinfunction "EP_EP6") (pintype "passive"))
      (node (ref "ESP1") (pin "EP7") (pinfunction "EP_EP7") (pintype "passive"))
      (node (ref "ESP1") (pin "EP8") (pinfunction "EP_EP8") (pintype "passive"))
      (node (ref "ESP1") (pin "EP9") (pinfunction "EP_EP9") (pintype "passive"))
      (node (ref "IC4") (pin "2") (pinfunction "GND_2") (pintype "power_in"))
      (node (ref "IC6") (pin "3") (pinfunction "GND_3") (pintype "power_in"))
      (node (ref "OK2") (pin "2") (pinfunction "C_2") (pintype "passive"))
      (node (ref "PGD") (pin "C") (pinfunction "C_C") (pintype "passive"))
      (node (ref "R11") (pin "1") (pinfunction "1_1") (pintype "passive"))
      (node (ref "R35") (pin "2") (pinfunction "2_2") (pintype "passive"))
      (node (ref "R42") (pin "2") (pinfunction "2_2") (pintype "passive"))
      (node (ref "R44") (pin "2") (pinfunction "2_2") (pintype "passive"))
      (node (ref "R47") (pin "2") (pinfunction "2_2") (pintype "passive"))
      (node (ref "R5") (pin "2") (pinfunction "2_2") (pintype "passive"))
      (node (ref "R8") (pin "1") (pinfunction "1_1") (pintype "passive"))
      (node (ref "RST") (pin "3") (pinfunction "3_3") (pintype "passive"))
      (node (ref "RST") (pin "4") (pinfunction "4_4") (pintype "passive"))
      (node (ref "U2") (pin "2") (pinfunction "GND_2") (pintype "power_in"))
      (node (ref "UEXT") (pin "2") (pinfunction "2_2") (pintype "passive"))
      (node (ref "USB") (pin "GND") (pinfunction "GND_GND") (pintype "bidirectional"))
      (node (ref "USB") (pin "MT1") (pinfunction "GND_MT1") (pintype "bidirectional"))
      (node (ref "USB") (pin "MT2") (pinfunction "GND_MT2") (pintype "bidirectional"))
      (node (ref "USB") (pin "MT3") (pinfunction "GND_MT3") (pintype "bidirectional"))
      (node (ref "USB") (pin "MT4") (pinfunction "GND_MT4") (pintype "bidirectional"))
      (node (ref "USB") (pin "MT5") (pinfunction "GND_MT5") (pintype "bidirectional"))
      (node (ref "USB") (pin "MT6") (pinfunction "GND_MT6") (pintype "bidirectional"))
      (node (ref "USD") (pin "6") (pinfunction "GND_6") (pintype "power_in"))
      (node (ref "USD") (pin "S1") (pinfunction "SHIELD_S1") (pintype "passive"))
      (node (ref "USD") (pin "S2") (pinfunction "SHIELD_S2") (pintype "passive"))
      (node (ref "USD") (pin "S3") (pinfunction "SHIELD_S3") (pintype "passive"))
      (node (ref "USD") (pin "S4") (pinfunction "SHIELD_S4") (pintype "passive"))
    )
    (net (code "30") (name "Net-(BSB-Pad1)") (class "Default")
      (node (ref "BSB") (pin "1") (pinfunction "1_1") (pintype "passive"))
      (node (ref "R10") (pin "1") (pinfunction "1_1") (pintype "passive"))
    )
    (net (code "31") (name "Net-(BSBB-1)") (class "Default")
      (node (ref "BSB") (pin "2") (pinfunction "1_2") (pintype "passive"))
      (node (ref "R9") (pin "1") (pinfunction "1_1") (pintype "passive"))
    )
    (net (code "32") (name "Net-(D2-PadC)") (class "Default")
      (node (ref "D2") (pin "C") (pinfunction "C_C") (pintype "passive"))
      (node (ref "D3") (pin "1") (pinfunction "1_1") (pintype "passive"))
      (node (ref "R9") (pin "2") (pinfunction "2_2") (pintype "passive"))
    )
    (net (code "33") (name "Net-(IC4-FB)") (class "Default")
      (node (ref "IC4") (pin "5") (pinfunction "FB_5") (pintype "input"))
      (node (ref "R40") (pin "1") (pinfunction "1_1") (pintype "passive"))
      (node (ref "R41") (pin "2") (pinfunction "2_2") (pintype "passive"))
    )
    (net (code "34") (name "Net-(IC4-LX)") (class "Default")
      (node (ref "IC4") (pin "3") (pinfunction "LX_3") (pintype "output"))
      (node (ref "L4") (pin "1") (pinfunction "1_1") (pintype "passive"))
    )
    (net (code "35") (name "Net-(IC6-TNOW{slash}~{DTR})") (class "Default")
      (node (ref "IC6") (pin "6") (pinfunction "TNOW/~{DTR}_6") (pintype "bidirectional"))
      (node (ref "Q5") (pin "2") (pinfunction "E_2") (pintype "passive"))
      (node (ref "R46") (pin "2") (pinfunction "2_2") (pintype "passive"))
      (node (ref "R50") (pin "1") (pinfunction "1_1") (pintype "passive"))
    )
    (net (code "36") (name "Net-(IC6-TXD)") (class "Default")
      (node (ref "IC6") (pin "8") (pinfunction "TXD_8") (pintype "output"))
      (node (ref "R49") (pin "1") (pinfunction "1_1") (pintype "passive"))
    )
    (net (code "37") (name "Net-(IC6-~{CTS})") (class "Default")
      (node (ref "IC6") (pin "5") (pinfunction "~{CTS}_5") (pintype "input"))
      (node (ref "R50") (pin "2") (pinfunction "2_2") (pintype "passive"))
    )
    (net (code "38") (name "Net-(IC6-~{RTS})") (class "Default")
      (node (ref "IC6") (pin "4") (pinfunction "~{RTS}_4") (pintype "output"))
      (node (ref "Q6") (pin "2") (pinfunction "E_2") (pintype "passive"))
      (node (ref "R45") (pin "2") (pinfunction "2_2") (pintype "passive"))
    )
    (net (code "39") (name "Net-(OK1-A)") (class "Default")
      (node (ref "OK1") (pin "1") (pinfunction "A_1") (pintype "passive"))
      (node (ref "R2") (pin "2") (pinfunction "2_2") (pintype "passive"))
    )
    (net (code "40") (name "Net-(OK1-BAS)") (class "Default")
      (node (ref "OK1") (pin "6") (pinfunction "BAS_6") (pintype "passive"))
      (node (ref "R4") (pin "2") (pinfunction "2_2") (pintype "passive"))
    )
    (net (code "41") (name "Net-(OK1-C)") (class "Default")
      (node (ref "ACT") (pin "A") (pinfunction "A_A") (pintype "passive"))
      (node (ref "OK1") (pin "2") (pinfunction "C_2") (pintype "passive"))
    )
    (net (code "42") (name "Net-(OK2-A)") (class "Default")
      (node (ref "OK2") (pin "1") (pinfunction "A_1") (pintype "passive"))
      (node (ref "R3") (pin "2") (pinfunction "2_2") (pintype "passive"))
    )
    (net (code "43") (name "Net-(OK2-BAS)") (class "Default")
      (node (ref "OK2") (pin "6") (pinfunction "BAS_6") (pintype "passive"))
      (node (ref "R1") (pin "2") (pinfunction "2_2") (pintype "passive"))
    )
    (net (code "44") (name "Net-(OK2-EMI)") (class "Default")
      (node (ref "OK2") (pin "4") (pinfunction "EMI_4") (pintype "passive"))
      (node (ref "Q1") (pin "1") (pinfunction "B_1") (pintype "passive"))
      (node (ref "R1") (pin "1") (pinfunction "1_1") (pintype "passive"))
      (node (ref "R7") (pin "2") (pinfunction "2_2") (pintype "passive"))
    )
    (net (code "45") (name "Net-(OPT-Pad2)") (class "Default")
      (node (ref "OPT") (pin "2") (pinfunction "2_2") (pintype "passive"))
      (node (ref "R35") (pin "1") (pinfunction "1_1") (pintype "passive"))
    )
    (net (code "46") (name "Net-(PGD-PadA)") (class "Default")
      (node (ref "PGD") (pin "A") (pinfunction "A_A") (pintype "passive"))
      (node (ref "R48") (pin "1") (pinfunction "1_1") (pintype "passive"))
    )
    (net (code "47") (name "Net-(Q2-PadB)") (class "Default")
      (node (ref "Q2") (pin "B") (pinfunction "B_B") (pintype "passive"))
      (node (ref "R6") (pin "1") (pinfunction "1_1") (pintype "passive"))
    )
    (net (code "48") (name "Net-(Q2-PadC)") (class "Default")
      (node (ref "Q2") (pin "C") (pinfunction "C_C") (pintype "passive"))
      (node (ref "R3") (pin "1") (pinfunction "1_1") (pintype "passive"))
    )
    (net (code "49") (name "Net-(Q5-B)") (class "Default")
      (node (ref "Q5") (pin "1") (pinfunction "B_1") (pintype "passive"))
      (node (ref "R45") (pin "1") (pinfunction "1_1") (pintype "passive"))
    )
    (net (code "50") (name "Net-(Q6-B)") (class "Default")
      (node (ref "Q6") (pin "1") (pinfunction "B_1") (pintype "passive"))
      (node (ref "R46") (pin "1") (pinfunction "1_1") (pintype "passive"))
    )
    (net (code "51") (name "Net-(R41-Pad1)") (class "Default")
      (node (ref "R41") (pin "1") (pinfunction "1_1") (pintype "passive"))
      (node (ref "R42") (pin "1") (pinfunction "1_1") (pintype "passive"))
    )
    (net (code "52") (name "Net-(USD-CS{slash}DAT3)") (class "Default")
      (node (ref "RN3") (pin "2") (pinfunction "2_2") (pintype "passive"))
      (node (ref "USD") (pin "2") (pinfunction "CS/DAT3_2") (pintype "bidirectional"))
    )
    (net (code "53") (name "Net-(USD-DAT0)") (class "Default")
      (node (ref "R31") (pin "2") (pinfunction "2_2") (pintype "passive"))
      (node (ref "USD") (pin "7") (pinfunction "DAT0_7") (pintype "bidirectional"))
    )
    (net (code "54") (name "Net-(USD-DAT1)") (class "Default")
      (node (ref "RN3") (pin "3") (pinfunction "3_3") (pintype "passive"))
      (node (ref "USD") (pin "8") (pinfunction "DAT1_8") (pintype "bidirectional"))
    )
    (net (code "55") (name "Net-(USD-DAT2)") (class "Default")
      (node (ref "RN3") (pin "1") (pinfunction "1_1") (pintype "passive"))
      (node (ref "USD") (pin "1") (pinfunction "DAT2_1") (pintype "bidirectional"))
    )
    (net (code "56") (name "Net-(USD-SCLK)") (class "Default")
      (node (ref "R33") (pin "2") (pinfunction "2_2") (pintype "passive"))
      (node (ref "USD") (pin "5") (pinfunction "SCLK_5") (pintype "bidirectional"))
    )
    (net (code "57") (name "PHY-PWR") (class "Default")
      (node (ref "ESP1") (pin "14") (pinfunction "GPIO12_14") (pintype "bidirectional"))
    )
    (net (code "58") (name "PWR-SNS") (class "Default")
      (node (ref "ESP1") (pin "5") (pinfunction "SENSOR_VN_5") (pintype "bidirectional"))
      (node (ref "R43") (pin "2") (pinfunction "2_2") (pintype "passive"))
      (node (ref "R44") (pin "1") (pinfunction "1_1") (pintype "passive"))
    )
    (net (code "59") (name "SD-VCC") (class "Default")
      (node (ref "C15") (pin "1") (pinfunction "1_1") (pintype "passive"))
      (node (ref "C16") (pin "1") (pinfunction "1_1") (pintype "passive"))
      (node (ref "L2") (pin "2") (pinfunction "2_2") (pintype "passive"))
      (node (ref "USD") (pin "4") (pinfunction "VCC_4") (pintype "power_in"))
    )
    (net (code "60") (name "SUP-12V0") (class "Default")
      (node (ref "12V") (pin "1") (pinfunction "1_1") (pintype "passive"))
      (node (ref "C18") (pin "+") (pinfunction "+_+") (pintype "passive"))
      (node (ref "C20") (pin "1") (pinfunction "1_1") (pintype "passive"))
      (node (ref "C22") (pin "1") (pinfunction "1_1") (pintype "passive"))
      (node (ref "D1") (pin "C") (pinfunction "C_C") (pintype "passive"))
      (node (ref "DC1") (pin "1") (pinfunction "+VIN_1") (pintype "passive"))
    )
    (net (code "61") (name "SUP-GND") (class "Default")
      (node (ref "12V") (pin "2") (pinfunction "1_2") (pintype "passive"))
      (node (ref "C18") (pin "-") (pinfunction "-_-") (pintype "passive"))
      (node (ref "C21") (pin "1") (pinfunction "1_1") (pintype "passive"))
      (node (ref "C22") (pin "2") (pinfunction "2_2") (pintype "passive"))
      (node (ref "D1") (pin "A") (pinfunction "A_A") (pintype "passive"))
      (node (ref "DC1") (pin "2") (pinfunction "-VIN_2") (pintype "passive"))
    )
    (net (code "62") (name "UEXT-RX") (class "Default")
      (node (ref "ESP1") (pin "7") (pinfunction "GPIO35_7") (pintype "bidirectional"))
      (node (ref "RN4") (pin "4") (pinfunction "4_4") (pintype "passive"))
      (node (ref "UEXT") (pin "4") (pinfunction "4_4") (pintype "passive"))
    )
    (net (code "63") (name "UEXT-TX") (class "Default")
      (node (ref "ESP1") (pin "9") (pinfunction "GPIO33_9") (pintype "bidirectional"))
      (node (ref "UEXT") (pin "3") (pinfunction "3_3") (pintype "passive"))
    )
    (net (code "64") (name "USB-D_N") (class "Default")
      (node (ref "IC6") (pin "2") (pinfunction "D-_2") (pintype "bidirectional"))
      (node (ref "U2") (pin "1") (pinfunction "IO1_1") (pintype "passive"))
      (node (ref "USB") (pin "D-") (pinfunction "D-_D-") (pintype "bidirectional"))
    )
    (net (code "65") (name "USB-D_P") (class "Default")
      (node (ref "IC6") (pin "1") (pinfunction "D+_1") (pintype "bidirectional"))
      (node (ref "U2") (pin "5") (pinfunction "IO4_5") (pintype "passive"))
      (node (ref "USB") (pin "D+") (pinfunction "D+_D+") (pintype "bidirectional"))
    )
    (net (code "66") (name "USB-VBUS") (class "Default")
      (node (ref "Q7") (pin "3") (pinfunction "D_3") (pintype "passive"))
      (node (ref "USB") (pin "VBUS") (pinfunction "VCC_VBUS") (pintype "bidirectional"))
    )
    (net (code "67") (name "unconnected-(RST-Pad1)") (class "Default")
      (node (ref "RST") (pin "1") (pinfunction "1_1") (pintype "passive"))
    )
    (net (code "68") (name "unconnected-(USB-PadID)") (class "Default")
      (node (ref "USB") (pin "ID") (pinfunction "ID_ID") (pintype "bidirectional"))
    )
    (net (code "69") (name "unconnected-(USD-CDET-Pad9)") (class "Default")
      (node (ref "USD") (pin "9") (pinfunction "CDET_9") (pintype "passive"))
    )
  )
)
